# ecen201_blank_pcb.net
KiCad netlist of a schematic drawn in Altium Designer
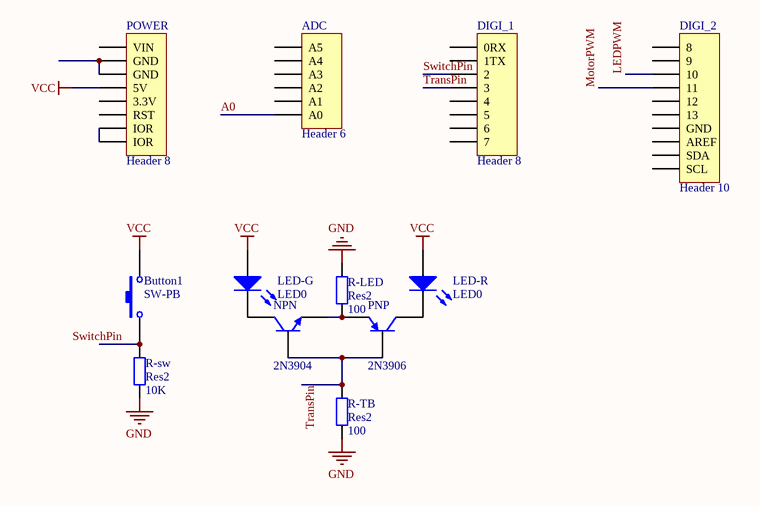
[diagram p0: ecen201_blank_pcb.SchDoc]

(export (version "E")
  (design (tool "Eeschema 10.0.6"))
  (components
    (comp (ref "ADC")
      (value "Header 6")
      (footprint "HDR1X6")
      (description "Header, 6-Pin")
      (fields (field (name "PUBLISHER") "Altium Limited"))
      (libsource (lib "Miscellaneous Connectors") (part "Header 6"))
    )
    (comp (ref "Button1")
      (value "SW-PB")
      (footprint "SPST-2")
      (description "Switch")
      (fields (field (name "PUBLISHER") "Altium Limited"))
      (libsource (lib "Miscellaneous Devices") (part "SW-PB"))
    )
    (comp (ref "DIGI_1")
      (value "Header 8")
      (footprint "HDR1X8")
      (description "Header, 8-Pin")
      (fields (field (name "PUBLISHER") "Altium Limited"))
      (libsource (lib "Miscellaneous Connectors") (part "Header 8"))
    )
    (comp (ref "DIGI_2")
      (value "Header 10")
      (footprint "HDR1X10")
      (description "Header, 10-Pin")
      (fields (field (name "PUBLISHER") "Altium Limited"))
      (libsource (lib "Miscellaneous Connectors") (part "Header 10"))
    )
    (comp (ref "LED-G")
      (value "LED0")
      (footprint "LED-0")
      (description "Typical INFRARED GaAs LED")
      (fields (field (name "PUBLISHER") "Altium Limited"))
      (libsource (lib "Miscellaneous Devices") (part "LED0"))
    )
    (comp (ref "LED-R")
      (value "LED0")
      (footprint "LED-0")
      (description "Typical INFRARED GaAs LED")
      (fields (field (name "PUBLISHER") "Altium Limited"))
      (libsource (lib "Miscellaneous Devices") (part "LED0"))
    )
    (comp (ref "NPN")
      (value "2N3904")
      (footprint "TO-92A")
      (description "NPN General Purpose Amplifier")
      (fields (field (name "PUBLISHER") "Altium Limited"))
      (libsource (lib "Miscellaneous Devices") (part "2N3904"))
    )
    (comp (ref "PNP")
      (value "2N3906")
      (footprint "TO-92A")
      (description "PNP General Purpose Amplifier")
      (fields (field (name "PUBLISHER") "Altium Limited"))
      (libsource (lib "Miscellaneous Devices") (part "2N3906"))
    )
    (comp (ref "POWER")
      (value "Header 8")
      (footprint "HDR1X8")
      (description "Header, 8-Pin")
      (fields (field (name "PUBLISHER") "Altium Limited"))
      (libsource (lib "Miscellaneous Connectors") (part "Header 8"))
    )
    (comp (ref "R-LED")
      (value "Res2")
      (footprint "AXIAL-0.4")
      (description "Resistor")
      (fields (field (name "ALTIUM_VALUE") "100") (field (name "PUBLISHER") "Altium Limited"))
      (libsource (lib "Miscellaneous Devices") (part "Res2"))
    )
    (comp (ref "R-sw")
      (value "Res2")
      (footprint "AXIAL-0.4")
      (description "Resistor")
      (fields (field (name "ALTIUM_VALUE") "10K") (field (name "PUBLISHER") "Altium Limited"))
      (libsource (lib "") (part "Res2_1"))
    )
    (comp (ref "R-TB")
      (value "Res2")
      (footprint "AXIAL-0.4")
      (description "Resistor")
      (fields (field (name "ALTIUM_VALUE") "100") (field (name "PUBLISHER") "Altium Limited"))
      (libsource (lib "") (part "Res2_1"))
    )
  )
  (nets
    (net (code "1") (name "/A0") (class "Default")
      (node (ref "ADC") (pin "6") (pinfunction "A0_6") (pintype "passive"))
    )
    (net (code "2") (name "/LEDPWM") (class "Default")
      (node (ref "DIGI_2") (pin "3") (pinfunction "10_3") (pintype "passive"))
    )
    (net (code "3") (name "/MotorPWM") (class "Default")
      (node (ref "DIGI_2") (pin "4") (pinfunction "11_4") (pintype "passive"))
    )
    (net (code "4") (name "/SwitchPin") (class "Default")
      (node (ref "DIGI_1") (pin "3") (pinfunction "GND_3") (pintype "passive"))
    )
    (net (code "5") (name "/TransPin") (class "Default")
      (node (ref "DIGI_1") (pin "4") (pinfunction "5V_4") (pintype "passive"))
      (node (ref "NPN") (pin "2") (pinfunction "B_2") (pintype "passive"))
      (node (ref "PNP") (pin "2") (pinfunction "B_2") (pintype "passive"))
      (node (ref "R-TB") (pin "2") (pinfunction "2_2") (pintype "passive"))
    )
    (net (code "6") (name "GND") (class "Default")
      (node (ref "R-LED") (pin "1") (pinfunction "1_1") (pintype "passive"))
      (node (ref "R-TB") (pin "1") (pinfunction "1_1") (pintype "passive"))
      (node (ref "R-sw") (pin "1") (pinfunction "1_1") (pintype "passive"))
    )
    (net (code "7") (name "Net-(Button1-Pad1)") (class "Default")
      (node (ref "Button1") (pin "1") (pinfunction "1_1") (pintype "passive"))
      (node (ref "R-sw") (pin "2") (pinfunction "2_2") (pintype "passive"))
    )
    (net (code "8") (name "Net-(LED-G-K)") (class "Default")
      (node (ref "LED-G") (pin "2") (pinfunction "K_2") (pintype "passive"))
      (node (ref "NPN") (pin "3") (pinfunction "C_3") (pintype "passive"))
    )
    (net (code "9") (name "Net-(LED-R-K)") (class "Default")
      (node (ref "LED-R") (pin "2") (pinfunction "K_2") (pintype "passive"))
      (node (ref "PNP") (pin "3") (pinfunction "C_3") (pintype "passive"))
    )
    (net (code "10") (name "Net-(NPN-E)") (class "Default")
      (node (ref "NPN") (pin "1") (pinfunction "E_1") (pintype "passive"))
      (node (ref "PNP") (pin "1") (pinfunction "E_1") (pintype "passive"))
      (node (ref "R-LED") (pin "2") (pinfunction "2_2") (pintype "passive"))
    )
    (net (code "11") (name "Net-(POWER-GND-Pad2)") (class "Default")
      (node (ref "POWER") (pin "2") (pinfunction "GND_2") (pintype "passive"))
      (node (ref "POWER") (pin "3") (pinfunction "GND_3") (pintype "passive"))
    )
    (net (code "12") (name "Net-(POWER-IOR-Pad7)") (class "Default")
      (node (ref "POWER") (pin "7") (pinfunction "IOR_7") (pintype "passive"))
      (node (ref "POWER") (pin "8") (pinfunction "IOR_8") (pintype "passive"))
    )
    (net (code "13") (name "VCC") (class "Default")
      (node (ref "Button1") (pin "2") (pinfunction "2_2") (pintype "passive"))
      (node (ref "LED-G") (pin "1") (pinfunction "A_1") (pintype "passive"))
      (node (ref "LED-R") (pin "1") (pinfunction "A_1") (pintype "passive"))
      (node (ref "POWER") (pin "4") (pinfunction "5V_4") (pintype "passive"))
    )
    (net (code "14") (name "unconnected-(ADC-A1-Pad5)") (class "Default")
      (node (ref "ADC") (pin "5") (pinfunction "A1_5") (pintype "passive"))
    )
    (net (code "15") (name "unconnected-(ADC-A2-Pad4)") (class "Default")
      (node (ref "ADC") (pin "4") (pinfunction "A2_4") (pintype "passive"))
    )
    (net (code "16") (name "unconnected-(ADC-A3-Pad3)") (class "Default")
      (node (ref "ADC") (pin "3") (pinfunction "A3_3") (pintype "passive"))
    )
    (net (code "17") (name "unconnected-(ADC-A4-Pad2)") (class "Default")
      (node (ref "ADC") (pin "2") (pinfunction "A4_2") (pintype "passive"))
    )
    (net (code "18") (name "unconnected-(ADC-A5-Pad1)") (class "Default")
      (node (ref "ADC") (pin "1") (pinfunction "A5_1") (pintype "passive"))
    )
    (net (code "19") (name "unconnected-(DIGI_1-3.3V-Pad5)") (class "Default")
      (node (ref "DIGI_1") (pin "5") (pinfunction "3.3V_5") (pintype "passive"))
    )
    (net (code "20") (name "unconnected-(DIGI_1-GND-Pad2)") (class "Default")
      (node (ref "DIGI_1") (pin "2") (pinfunction "GND_2") (pintype "passive"))
    )
    (net (code "21") (name "unconnected-(DIGI_1-IOR-Pad7)") (class "Default")
      (node (ref "DIGI_1") (pin "7") (pinfunction "IOR_7") (pintype "passive"))
    )
    (net (code "22") (name "unconnected-(DIGI_1-IOR-Pad8)") (class "Default")
      (node (ref "DIGI_1") (pin "8") (pinfunction "IOR_8") (pintype "passive"))
    )
    (net (code "23") (name "unconnected-(DIGI_1-RST-Pad6)") (class "Default")
      (node (ref "DIGI_1") (pin "6") (pinfunction "RST_6") (pintype "passive"))
    )
    (net (code "24") (name "unconnected-(DIGI_1-VIN-Pad1)") (class "Default")
      (node (ref "DIGI_1") (pin "1") (pinfunction "VIN_1") (pintype "passive"))
    )
    (net (code "25") (name "unconnected-(DIGI_2-8-Pad1)") (class "Default")
      (node (ref "DIGI_2") (pin "1") (pinfunction "8_1") (pintype "passive"))
    )
    (net (code "26") (name "unconnected-(DIGI_2-9-Pad2)") (class "Default")
      (node (ref "DIGI_2") (pin "2") (pinfunction "9_2") (pintype "passive"))
    )
    (net (code "27") (name "unconnected-(DIGI_2-12-Pad5)") (class "Default")
      (node (ref "DIGI_2") (pin "5") (pinfunction "12_5") (pintype "passive"))
    )
    (net (code "28") (name "unconnected-(DIGI_2-13-Pad6)") (class "Default")
      (node (ref "DIGI_2") (pin "6") (pinfunction "13_6") (pintype "passive"))
    )
    (net (code "29") (name "unconnected-(DIGI_2-AREF-Pad8)") (class "Default")
      (node (ref "DIGI_2") (pin "8") (pinfunction "AREF_8") (pintype "passive"))
    )
    (net (code "30") (name "unconnected-(DIGI_2-GND-Pad7)") (class "Default")
      (node (ref "DIGI_2") (pin "7") (pinfunction "GND_7") (pintype "passive"))
    )
    (net (code "31") (name "unconnected-(DIGI_2-SCL-Pad10)") (class "Default")
      (node (ref "DIGI_2") (pin "10") (pinfunction "SCL_10") (pintype "passive"))
    )
    (net (code "32") (name "unconnected-(DIGI_2-SDA-Pad9)") (class "Default")
      (node (ref "DIGI_2") (pin "9") (pinfunction "SDA_9") (pintype "passive"))
    )
    (net (code "33") (name "unconnected-(POWER-3.3V-Pad5)") (class "Default")
      (node (ref "POWER") (pin "5") (pinfunction "3.3V_5") (pintype "passive"))
    )
    (net (code "34") (name "unconnected-(POWER-RST-Pad6)") (class "Default")
      (node (ref "POWER") (pin "6") (pinfunction "RST_6") (pintype "passive"))
    )
    (net (code "35") (name "unconnected-(POWER-VIN-Pad1)") (class "Default")
      (node (ref "POWER") (pin "1") (pinfunction "VIN_1") (pintype "passive"))
    )
  )
)
